# LED_indicators.net
KiCad netlist of a schematic drawn in Altium Designer
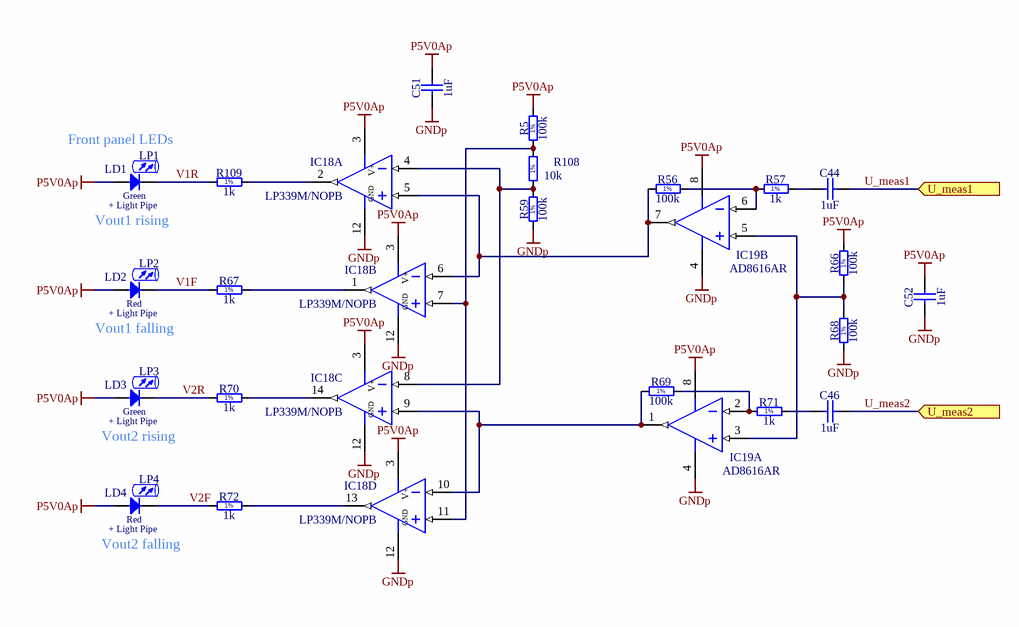
[diagram p0: LED_indicators.SchDoc]

(export (version "E")
  (design (tool "Eeschema 10.0.6"))
  (components
    (comp (ref "C44")
      (value "1uF")
      (footprint "CAPC1005X55N")
      (description "Non-polarised capacitor")
      (fields
        (field (name "PART NUMBER") "CC0402_1UF_16V_10%_X5R")
        (field (name "VOLTAGE") "16V")
        (field (name "AUTHOR") "CERN DEM JLC")
      )
      (libsource (lib "Capacitors") (part "Capacitor - non polarized"))
    )
    (comp (ref "C46")
      (value "1uF")
      (footprint "CAPC1005X55N")
      (description "Non-polarised capacitor")
      (fields
        (field (name "PART NUMBER") "CC0402_1UF_16V_10%_X5R")
        (field (name "VOLTAGE") "16V")
        (field (name "AUTHOR") "CERN DEM JLC")
      )
      (libsource (lib "Capacitors") (part "Capacitor - non polarized"))
    )
    (comp (ref "C51")
      (value "1uF")
      (footprint "CAPC1005X55N")
      (description "Non-polarised capacitor")
      (fields
        (field (name "PART NUMBER") "CC0402_1UF_16V_10%_X5R")
        (field (name "VOLTAGE") "16V")
        (field (name "AUTHOR") "CERN DEM JLC")
      )
      (libsource (lib "Capacitors") (part "Capacitor - non polarized"))
    )
    (comp (ref "C52")
      (value "1uF")
      (footprint "CAPC1005X55N")
      (description "Non-polarised capacitor")
      (fields
        (field (name "PART NUMBER") "CC0402_1UF_16V_10%_X5R")
        (field (name "VOLTAGE") "16V")
        (field (name "AUTHOR") "CERN DEM JLC")
      )
      (libsource (lib "Capacitors") (part "Capacitor - non polarized"))
    )
    (comp (ref "IC18")
      (value "LP339M/NOPB")
      (footprint "SOIC127P600X175-14N")
      (description "Quad Operational Amplifier")
      (fields (field (name "MANUFACTURER") "TEXAS INSTRUMENTS") (field (name "AUTHOR") "CERN DEM MR"))
      (libsource (lib "ICs And Semiconductors") (part "Operational Amplifier x4 Type5"))
    )
    (comp (ref "IC19")
      (value "AD8616AR")
      (footprint "ADI-R-8_N")
      (fields
        (field (name "MANUFACTURER") "Analog Devices")
        (field (name "GENERIC PART NUMBER") "AD8616")
        (field (name "MANUFACTURER1 PART NUMBER") "OPA2320SAIDGSR")
      )
      (libsource (lib "Altium Content Vault") (part "ADI-OP29X-R-8"))
    )
    (comp (ref "LD1")
      (value "Green")
      (footprint "LED_DIALIGHT_555-230")
      (description "LED Green 1C 2A")
      (fields
        (field (name "PART NUMBER") "LED_DIALIGHT_555-2301F")
        (field (name "MANUFACTURER") "DIALIGHT")
        (field (name "AUTHOR") "CERN DEM JMW")
      )
      (libsource (lib "ICs And Semiconductors") (part "LED Green 1C 2A"))
    )
    (comp (ref "LD2")
      (value "Red")
      (footprint "LED_DIALIGHT_555-200")
      (description "LED Red 1C 2A")
      (fields
        (field (name "PART NUMBER") "LED_DIALIGHT_555-2001F")
        (field (name "MANUFACTURER") "DIALIGHT")
        (field (name "AUTHOR") "CERN DEM JMW")
      )
      (libsource (lib "ICs And Semiconductors") (part "LED Red 1C 2A"))
    )
    (comp (ref "LD3")
      (value "Green")
      (footprint "LED_DIALIGHT_555-230")
      (description "LED Green 1C 2A")
      (fields
        (field (name "PART NUMBER") "LED_DIALIGHT_555-2301F")
        (field (name "MANUFACTURER") "DIALIGHT")
        (field (name "AUTHOR") "CERN DEM JMW")
      )
      (libsource (lib "ICs And Semiconductors") (part "LED Green 1C 2A"))
    )
    (comp (ref "LD4")
      (value "Red")
      (footprint "LED_DIALIGHT_555-200")
      (description "LED Red 1C 2A")
      (fields
        (field (name "PART NUMBER") "LED_DIALIGHT_555-2001F")
        (field (name "MANUFACTURER") "DIALIGHT")
        (field (name "AUTHOR") "CERN DEM JMW")
      )
      (libsource (lib "ICs And Semiconductors") (part "LED Red 1C 2A"))
    )
    (comp (ref "LP1")
      (value "~")
      (footprint "LEDLP_BIVAR_PLP2-1200")
      (description "LED Light Pipe x1 Type1")
      (fields
        (field (name "PART NUMBER") "LEDLP_BIVAR_PLP2-1200")
        (field (name "MANUFACTURER") "BIVAR")
        (field (name "AUTHOR") "CERN DEM HF")
      )
      (libsource (lib "ICs And Semiconductors") (part "LED Light Pipe x1 Type1"))
    )
    (comp (ref "LP2")
      (value "~")
      (footprint "LEDLP_BIVAR_PLP2-1200")
      (description "LED Light Pipe x1 Type1")
      (fields
        (field (name "PART NUMBER") "LEDLP_BIVAR_PLP2-1200")
        (field (name "MANUFACTURER") "BIVAR")
        (field (name "AUTHOR") "CERN DEM HF")
      )
      (libsource (lib "ICs And Semiconductors") (part "LED Light Pipe x1 Type1"))
    )
    (comp (ref "LP3")
      (value "~")
      (footprint "LEDLP_BIVAR_PLP2-1200")
      (description "LED Light Pipe x1 Type1")
      (fields
        (field (name "PART NUMBER") "LEDLP_BIVAR_PLP2-1200")
        (field (name "MANUFACTURER") "BIVAR")
        (field (name "AUTHOR") "CERN DEM HF")
      )
      (libsource (lib "ICs And Semiconductors") (part "LED Light Pipe x1 Type1"))
    )
    (comp (ref "LP4")
      (value "~")
      (footprint "LEDLP_BIVAR_PLP2-1200")
      (description "LED Light Pipe x1 Type1")
      (fields
        (field (name "PART NUMBER") "LEDLP_BIVAR_PLP2-1200")
        (field (name "MANUFACTURER") "BIVAR")
        (field (name "AUTHOR") "CERN DEM HF")
      )
      (libsource (lib "ICs And Semiconductors") (part "LED Light Pipe x1 Type1"))
    )
    (comp (ref "R5")
      (value "100k")
      (footprint "RESC1608X55N")
      (description "Resistor - 1%")
      (fields
        (field (name "PART NUMBER") "R0603_100K_1%_0.1W_100PPM")
        (field (name "POWER") "0.1W")
        (field (name "AUTHOR") "CERN DEM JLC")
      )
      (libsource (lib "Resistors") (part "Resistor - 1%"))
    )
    (comp (ref "R56")
      (value "100k")
      (footprint "RESC1608X55N")
      (description "Resistor - 1%")
      (fields
        (field (name "PART NUMBER") "R0603_100K_1%_0.1W_100PPM")
        (field (name "POWER") "0.1W")
        (field (name "AUTHOR") "CERN DEM JLC")
      )
      (libsource (lib "Resistors") (part "Resistor - 1%"))
    )
    (comp (ref "R57")
      (value "1k")
      (footprint "RESC1005X40N")
      (description "Resistor - 1%")
      (fields
        (field (name "PART NUMBER") "R0402_1K_1%_0.0625W_100PPM")
        (field (name "POWER") "0.0625W")
        (field (name "AUTHOR") "CERN DEM JLC")
      )
      (libsource (lib "Resistors") (part "Resistor - 1%"))
    )
    (comp (ref "R59")
      (value "100k")
      (footprint "RESC1608X55N")
      (description "Resistor - 1%")
      (fields
        (field (name "PART NUMBER") "R0603_100K_1%_0.1W_100PPM")
        (field (name "POWER") "0.1W")
        (field (name "AUTHOR") "CERN DEM JLC")
      )
      (libsource (lib "Resistors") (part "Resistor - 1%"))
    )
    (comp (ref "R66")
      (value "100k")
      (footprint "RESC1608X55N")
      (description "Resistor - 1%")
      (fields
        (field (name "PART NUMBER") "R0603_100K_1%_0.1W_100PPM")
        (field (name "POWER") "0.1W")
        (field (name "AUTHOR") "CERN DEM JLC")
      )
      (libsource (lib "Resistors") (part "Resistor - 1%"))
    )
    (comp (ref "R67")
      (value "1k")
      (footprint "RESC1005X40N")
      (description "Resistor - 1%")
      (fields
        (field (name "PART NUMBER") "R0402_1K_1%_0.0625W_100PPM")
        (field (name "POWER") "0.0625W")
        (field (name "AUTHOR") "CERN DEM JLC")
      )
      (libsource (lib "Resistors") (part "Resistor - 1%"))
    )
    (comp (ref "R68")
      (value "100k")
      (footprint "RESC1608X55N")
      (description "Resistor - 1%")
      (fields
        (field (name "PART NUMBER") "R0603_100K_1%_0.1W_100PPM")
        (field (name "POWER") "0.1W")
        (field (name "AUTHOR") "CERN DEM JLC")
      )
      (libsource (lib "Resistors") (part "Resistor - 1%"))
    )
    (comp (ref "R69")
      (value "100k")
      (footprint "RESC1608X55N")
      (description "Resistor - 1%")
      (fields
        (field (name "PART NUMBER") "R0603_100K_1%_0.1W_100PPM")
        (field (name "POWER") "0.1W")
        (field (name "AUTHOR") "CERN DEM JLC")
      )
      (libsource (lib "Resistors") (part "Resistor - 1%"))
    )
    (comp (ref "R70")
      (value "1k")
      (footprint "RESC1005X40N")
      (description "Resistor - 1%")
      (fields
        (field (name "PART NUMBER") "R0402_1K_1%_0.0625W_100PPM")
        (field (name "POWER") "0.0625W")
        (field (name "AUTHOR") "CERN DEM JLC")
      )
      (libsource (lib "Resistors") (part "Resistor - 1%"))
    )
    (comp (ref "R71")
      (value "1k")
      (footprint "RESC1005X40N")
      (description "Resistor - 1%")
      (fields
        (field (name "PART NUMBER") "R0402_1K_1%_0.0625W_100PPM")
        (field (name "POWER") "0.0625W")
        (field (name "AUTHOR") "CERN DEM JLC")
      )
      (libsource (lib "Resistors") (part "Resistor - 1%"))
    )
    (comp (ref "R72")
      (value "1k")
      (footprint "RESC1005X40N")
      (description "Resistor - 1%")
      (fields
        (field (name "PART NUMBER") "R0402_1K_1%_0.0625W_100PPM")
        (field (name "POWER") "0.0625W")
        (field (name "AUTHOR") "CERN DEM JLC")
      )
      (libsource (lib "Resistors") (part "Resistor - 1%"))
    )
    (comp (ref "R108")
      (value "10k")
      (footprint "RESC1005X40N")
      (description "Resistor - 1%")
      (fields
        (field (name "PART NUMBER") "R0402_10K_1%_0.0625W_100PPM")
        (field (name "POWER") "0.0625W")
        (field (name "AUTHOR") "CERN DEM JLC")
      )
      (libsource (lib "Resistors") (part "Resistor - 1%"))
    )
    (comp (ref "R109")
      (value "1k")
      (footprint "RESC1005X40N")
      (description "Resistor - 1%")
      (fields
        (field (name "PART NUMBER") "R0402_1K_1%_0.0625W_100PPM")
        (field (name "POWER") "0.0625W")
        (field (name "AUTHOR") "CERN DEM JLC")
      )
      (libsource (lib "Resistors") (part "Resistor - 1%"))
    )
  )
  (nets
    (net (code "1") (name "/U_meas1") (class "Default")
      (node (ref "C44") (pin "2") (pinfunction "2_2") (pintype "passive"))
    )
    (net (code "2") (name "/U_meas2") (class "Default")
      (node (ref "C46") (pin "2") (pinfunction "2_2") (pintype "passive"))
    )
    (net (code "3") (name "/V1F") (class "Default")
      (node (ref "LD2") (pin "1") (pinfunction "C_1") (pintype "passive"))
      (node (ref "R67") (pin "1") (pinfunction "1_1") (pintype "passive"))
    )
    (net (code "4") (name "/V1R") (class "Default")
      (node (ref "LD1") (pin "1") (pinfunction "C_1") (pintype "passive"))
      (node (ref "R109") (pin "1") (pinfunction "1_1") (pintype "passive"))
    )
    (net (code "5") (name "/V2F") (class "Default")
      (node (ref "LD4") (pin "1") (pinfunction "C_1") (pintype "passive"))
      (node (ref "R72") (pin "1") (pinfunction "1_1") (pintype "passive"))
    )
    (net (code "6") (name "/V2R") (class "Default")
      (node (ref "LD3") (pin "1") (pinfunction "C_1") (pintype "passive"))
      (node (ref "R70") (pin "1") (pinfunction "1_1") (pintype "passive"))
    )
    (net (code "7") (name "GNDp") (class "Default")
      (node (ref "C51") (pin "1") (pinfunction "1_1") (pintype "passive"))
      (node (ref "C52") (pin "1") (pinfunction "1_1") (pintype "passive"))
      (node (ref "IC18") (pin "12") (pinfunction "GND_12") (pintype "power_in"))
      (node (ref "IC19") (pin "4") (pinfunction "-V_4") (pintype "power_in"))
      (node (ref "R59") (pin "1") (pinfunction "1_1") (pintype "passive"))
      (node (ref "R68") (pin "1") (pinfunction "1_1") (pintype "passive"))
    )
    (net (code "8") (name "Net-(C44-Pad1)") (class "Default")
      (node (ref "C44") (pin "1") (pinfunction "1_1") (pintype "passive"))
      (node (ref "R57") (pin "2") (pinfunction "2_2") (pintype "passive"))
    )
    (net (code "9") (name "Net-(C46-Pad1)") (class "Default")
      (node (ref "C46") (pin "1") (pinfunction "1_1") (pintype "passive"))
      (node (ref "R71") (pin "2") (pinfunction "2_2") (pintype "passive"))
    )
    (net (code "10") (name "Net-(IC18A-IN+)") (class "Default")
      (node (ref "IC18") (pin "5") (pinfunction "IN+_5") (pintype "input"))
      (node (ref "IC18") (pin "6") (pinfunction "IN-_6") (pintype "input"))
      (node (ref "IC19") (pin "7") (pinfunction "OUT_B_7") (pintype "output"))
      (node (ref "R56") (pin "1") (pinfunction "1_1") (pintype "passive"))
    )
    (net (code "11") (name "Net-(IC18A-IN-)") (class "Default")
      (node (ref "IC18") (pin "4") (pinfunction "IN-_4") (pintype "input"))
      (node (ref "IC18") (pin "8") (pinfunction "IN-_8") (pintype "input"))
      (node (ref "R108") (pin "1") (pinfunction "1_1") (pintype "passive"))
      (node (ref "R59") (pin "2") (pinfunction "2_2") (pintype "passive"))
    )
    (net (code "12") (name "Net-(IC18A-OUT)") (class "Default")
      (node (ref "IC18") (pin "2") (pinfunction "OUT_2") (pintype "output"))
      (node (ref "R109") (pin "2") (pinfunction "2_2") (pintype "passive"))
    )
    (net (code "13") (name "Net-(IC18B-IN+)") (class "Default")
      (node (ref "IC18") (pin "11") (pinfunction "IN+_11") (pintype "input"))
      (node (ref "IC18") (pin "7") (pinfunction "IN+_7") (pintype "input"))
      (node (ref "R108") (pin "2") (pinfunction "2_2") (pintype "passive"))
      (node (ref "R5") (pin "1") (pinfunction "1_1") (pintype "passive"))
    )
    (net (code "14") (name "Net-(IC18B-OUT)") (class "Default")
      (node (ref "IC18") (pin "1") (pinfunction "OUT_1") (pintype "output"))
      (node (ref "R67") (pin "2") (pinfunction "2_2") (pintype "passive"))
    )
    (net (code "15") (name "Net-(IC18C-IN+)") (class "Default")
      (node (ref "IC18") (pin "10") (pinfunction "IN-_10") (pintype "input"))
      (node (ref "IC18") (pin "9") (pinfunction "IN+_9") (pintype "input"))
      (node (ref "IC19") (pin "1") (pinfunction "OUT_A_1") (pintype "output"))
      (node (ref "R69") (pin "1") (pinfunction "1_1") (pintype "passive"))
    )
    (net (code "16") (name "Net-(IC18C-OUT)") (class "Default")
      (node (ref "IC18") (pin "14") (pinfunction "OUT_14") (pintype "output"))
      (node (ref "R70") (pin "2") (pinfunction "2_2") (pintype "passive"))
    )
    (net (code "17") (name "Net-(IC18D-OUT)") (class "Default")
      (node (ref "IC18") (pin "13") (pinfunction "OUT_13") (pintype "output"))
      (node (ref "R72") (pin "2") (pinfunction "2_2") (pintype "passive"))
    )
    (net (code "18") (name "Net-(IC19A-+IN_A)") (class "Default")
      (node (ref "IC19") (pin "3") (pinfunction "+IN_A_3") (pintype "input"))
      (node (ref "IC19") (pin "5") (pinfunction "+IN_B_5") (pintype "input"))
      (node (ref "R66") (pin "1") (pinfunction "1_1") (pintype "passive"))
      (node (ref "R68") (pin "2") (pinfunction "2_2") (pintype "passive"))
    )
    (net (code "19") (name "Net-(IC19A--IN_A)") (class "Default")
      (node (ref "IC19") (pin "2") (pinfunction "-IN_A_2") (pintype "input"))
      (node (ref "R69") (pin "2") (pinfunction "2_2") (pintype "passive"))
      (node (ref "R71") (pin "1") (pinfunction "1_1") (pintype "passive"))
    )
    (net (code "20") (name "Net-(IC19B--IN_B)") (class "Default")
      (node (ref "IC19") (pin "6") (pinfunction "-IN_B_6") (pintype "input"))
      (node (ref "R56") (pin "2") (pinfunction "2_2") (pintype "passive"))
      (node (ref "R57") (pin "1") (pinfunction "1_1") (pintype "passive"))
    )
    (net (code "21") (name "P5V0Ap") (class "Default")
      (node (ref "C51") (pin "2") (pinfunction "2_2") (pintype "passive"))
      (node (ref "C52") (pin "2") (pinfunction "2_2") (pintype "passive"))
      (node (ref "IC18") (pin "3") (pinfunction "V+_3") (pintype "power_in"))
      (node (ref "IC19") (pin "8") (pinfunction "+V_8") (pintype "power_in"))
      (node (ref "LD1") (pin "2") (pinfunction "A_2") (pintype "passive"))
      (node (ref "LD2") (pin "2") (pinfunction "A_2") (pintype "passive"))
      (node (ref "LD3") (pin "2") (pinfunction "A_2") (pintype "passive"))
      (node (ref "LD4") (pin "2") (pinfunction "A_2") (pintype "passive"))
      (node (ref "R5") (pin "2") (pinfunction "2_2") (pintype "passive"))
      (node (ref "R66") (pin "2") (pinfunction "2_2") (pintype "passive"))
    )
  )
)
